# FPGA.net
KiCad netlist of a schematic drawn in EAGLE
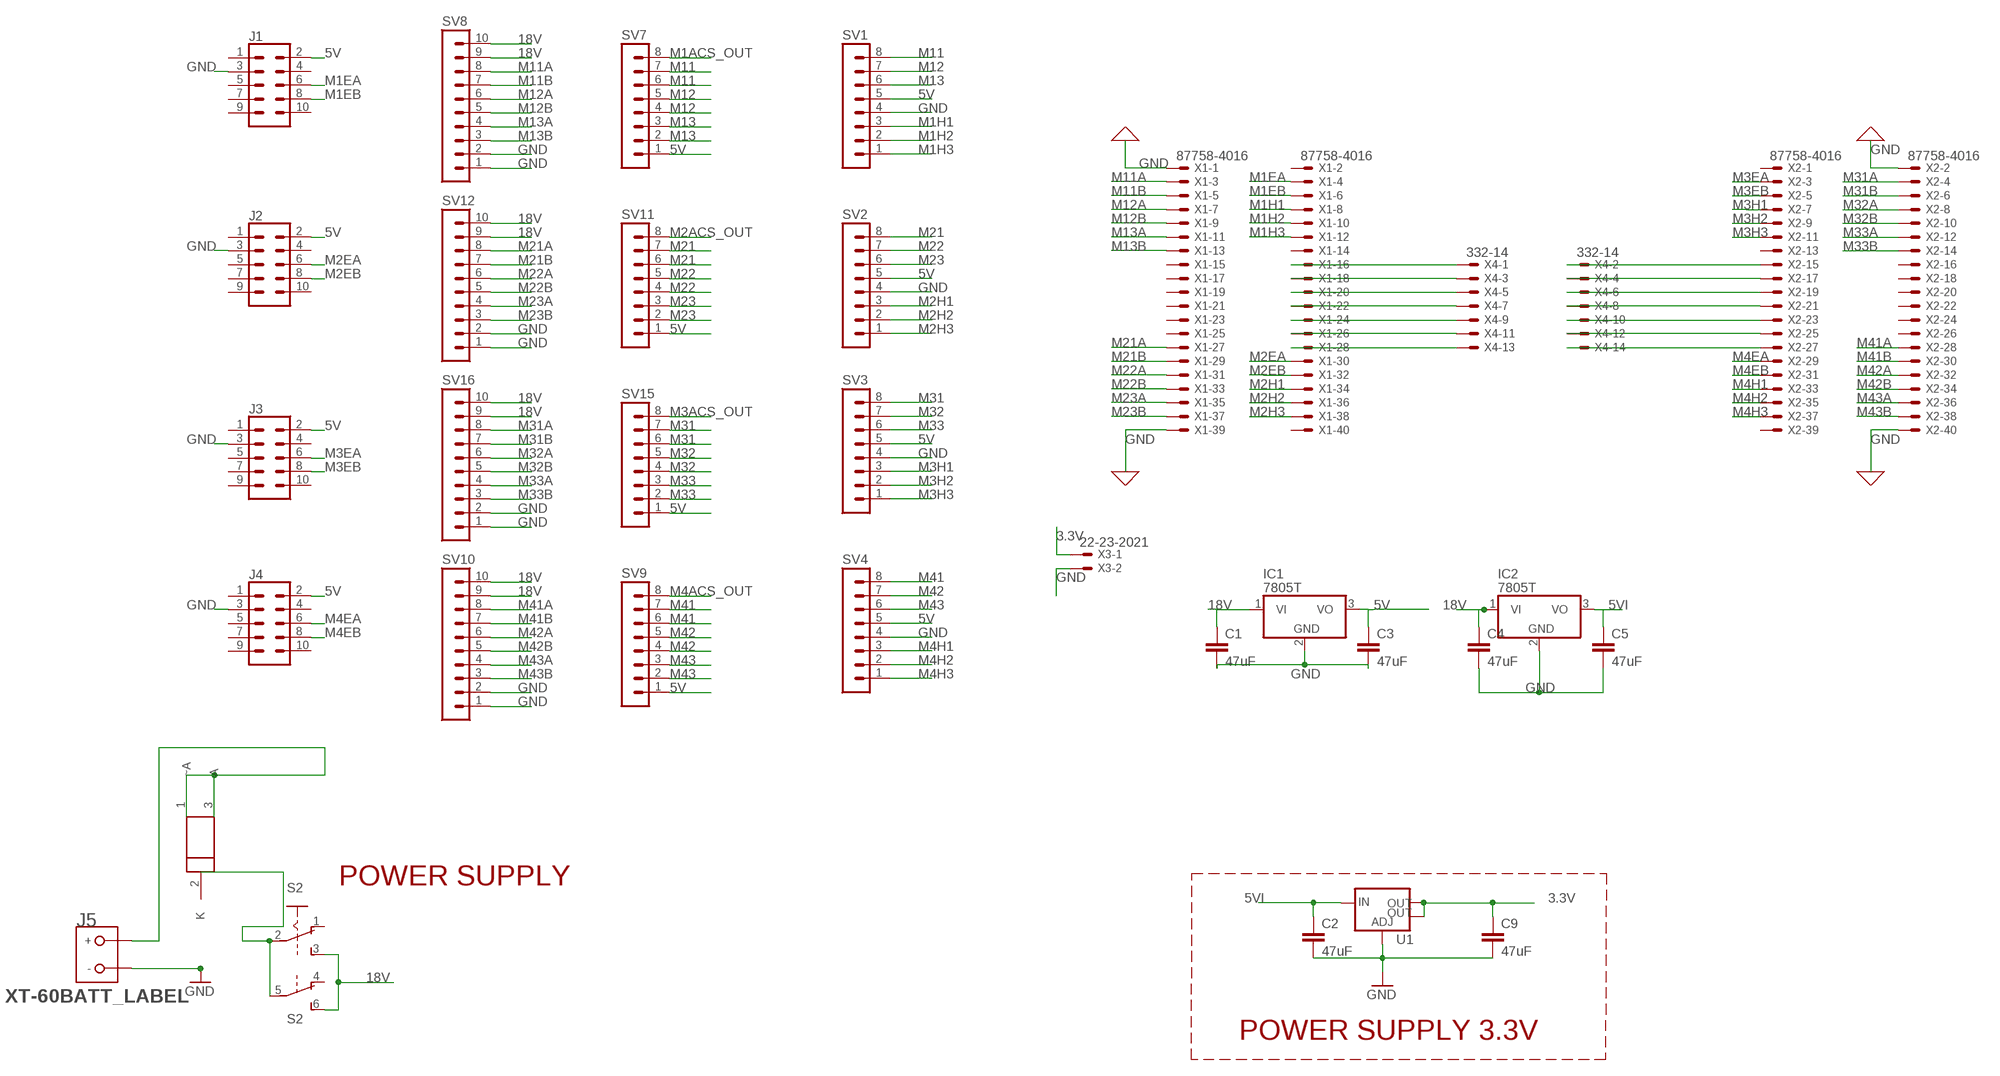
[diagram p0: schematic, sheet 1]

(export (version "E")
  (design (tool "Eeschema 10.0.6"))
  (components
    (comp (ref "C1")
      (value "47uF")
      (footprint "eagle-import:C1206")
      (libsource (lib "eagle-import") (part "C-EUC1206"))
    )
    (comp (ref "C2")
      (value "47uF")
      (footprint "eagle-import:C1206")
      (libsource (lib "eagle-import") (part "C-EUC1206"))
    )
    (comp (ref "C3")
      (value "47uF")
      (footprint "eagle-import:C1206")
      (libsource (lib "eagle-import") (part "C-EUC1206"))
    )
    (comp (ref "C4")
      (value "47uF")
      (footprint "eagle-import:C1206")
      (libsource (lib "eagle-import") (part "C-EUC1206"))
    )
    (comp (ref "C5")
      (value "47uF")
      (footprint "eagle-import:C1206")
      (libsource (lib "eagle-import") (part "C-EUC1206"))
    )
    (comp (ref "C9")
      (value "47uF")
      (footprint "eagle-import:C1206")
      (libsource (lib "eagle-import") (part "C-EUC1206"))
    )
    (comp (ref "IC1")
      (value "7805T")
      (footprint "eagle-import:TO220H")
      (libsource (lib "eagle-import") (part "78T05"))
    )
    (comp (ref "IC2")
      (value "7805T")
      (footprint "eagle-import:TO220H")
      (libsource (lib "eagle-import") (part "78T05"))
    )
    (comp (ref "J1")
      (value "CONN_05X2SHD_LOCK")
      (footprint "eagle-import:2X5-SHROUDED_LOCK")
      (libsource (lib "eagle-import") (part "CONN_05X2SHD_LOCK"))
    )
    (comp (ref "J2")
      (value "CONN_05X2SHD_LOCK")
      (footprint "eagle-import:2X5-SHROUDED_LOCK")
      (libsource (lib "eagle-import") (part "CONN_05X2SHD_LOCK"))
    )
    (comp (ref "J3")
      (value "CONN_05X2SHD_LOCK")
      (footprint "eagle-import:2X5-SHROUDED_LOCK")
      (libsource (lib "eagle-import") (part "CONN_05X2SHD_LOCK"))
    )
    (comp (ref "J4")
      (value "CONN_05X2SHD_LOCK")
      (footprint "eagle-import:2X5-SHROUDED_LOCK")
      (libsource (lib "eagle-import") (part "CONN_05X2SHD_LOCK"))
    )
    (comp (ref "J5")
      (value "XT-60BATT_LABEL")
      (footprint "eagle-import:XT-60")
      (libsource (lib "eagle-import") (part "XT-60BATT_LABEL"))
    )
    (comp (ref "S2")
      (value "A68-A31")
      (footprint "eagle-import:A68-A31")
      (libsource (lib "eagle-import") (part "A68-A31"))
    )
    (comp (ref "SV1")
      (value "MA08-1")
      (footprint "eagle-import:MA08-1")
      (libsource (lib "eagle-import") (part "MA08-1"))
    )
    (comp (ref "SV2")
      (value "MA08-1")
      (footprint "eagle-import:MA08-1")
      (libsource (lib "eagle-import") (part "MA08-1"))
    )
    (comp (ref "SV3")
      (value "MA08-1")
      (footprint "eagle-import:MA08-1")
      (libsource (lib "eagle-import") (part "MA08-1"))
    )
    (comp (ref "SV4")
      (value "MA08-1")
      (footprint "eagle-import:MA08-1")
      (libsource (lib "eagle-import") (part "MA08-1"))
    )
    (comp (ref "SV7")
      (value "MA08-1")
      (footprint "eagle-import:MA08-1")
      (libsource (lib "eagle-import") (part "MA08-1"))
    )
    (comp (ref "SV8")
      (value "MA10-1")
      (footprint "eagle-import:MA10-1")
      (libsource (lib "eagle-import") (part "MA10-1"))
    )
    (comp (ref "SV9")
      (value "MA08-1")
      (footprint "eagle-import:MA08-1")
      (libsource (lib "eagle-import") (part "MA08-1"))
    )
    (comp (ref "SV10")
      (value "MA10-1")
      (footprint "eagle-import:MA10-1")
      (libsource (lib "eagle-import") (part "MA10-1"))
    )
    (comp (ref "SV11")
      (value "MA08-1")
      (footprint "eagle-import:MA08-1")
      (libsource (lib "eagle-import") (part "MA08-1"))
    )
    (comp (ref "SV12")
      (value "MA10-1")
      (footprint "eagle-import:MA10-1")
      (libsource (lib "eagle-import") (part "MA10-1"))
    )
    (comp (ref "SV15")
      (value "MA08-1")
      (footprint "eagle-import:MA08-1")
      (libsource (lib "eagle-import") (part "MA08-1"))
    )
    (comp (ref "SV16")
      (value "MA10-1")
      (footprint "eagle-import:MA10-1")
      (libsource (lib "eagle-import") (part "MA10-1"))
    )
    (comp (ref "U1")
      (value "V_REG_LM1117SOT223")
      (footprint "eagle-import:SOT223")
      (libsource (lib "eagle-import") (part "V_REG_LM1117SOT223"))
    )
    (comp (ref "U3")
      (value "LP38690DT-3.3")
      (footprint "eagle-import:TO228P1042X238-3N")
      (libsource (lib "eagle-import") (part "LP38690DT-3.3"))
    )
    (comp (ref "X1")
      (value "87758-4016")
      (footprint "eagle-import:87758-4016")
      (fields (field (name "MF") "MOLEX"))
      (libsource (lib "eagle-import") (part "87758-4016"))
    )
    (comp (ref "X2")
      (value "87758-4016")
      (footprint "eagle-import:87758-4016")
      (fields (field (name "MF") "MOLEX"))
      (libsource (lib "eagle-import") (part "87758-4016"))
    )
    (comp (ref "X3")
      (value "22-23-2021")
      (footprint "eagle-import:22-23-2021")
      (fields (field (name "MF") "MOLEX"))
      (libsource (lib "eagle-import") (part "22-23-2021"))
    )
    (comp (ref "X4")
      (value "332-14")
      (footprint "eagle-import:332-14")
      (libsource (lib "eagle-import") (part "332-14"))
    )
  )
  (nets
    (net (code "1") (name "/3.3V") (class "Default")
      (node (ref "C9") (pin "1") (pinfunction "1_1") (pintype "passive"))
      (node (ref "U1") (pin "2") (pinfunction "OUT_2") (pintype "output"))
      (node (ref "U1") (pin "4") (pinfunction "OUT_4") (pintype "output"))
      (node (ref "X3") (pin "1") (pinfunction "S_1") (pintype "passive"))
    )
    (net (code "2") (name "/5V") (class "Default")
      (node (ref "C3") (pin "1") (pinfunction "1_1") (pintype "passive"))
      (node (ref "IC1") (pin "3") (pinfunction "VO_3") (pintype "passive"))
      (node (ref "J1") (pin "2") (pinfunction "2_2") (pintype "passive"))
      (node (ref "J2") (pin "2") (pinfunction "2_2") (pintype "passive"))
      (node (ref "J3") (pin "2") (pinfunction "2_2") (pintype "passive"))
      (node (ref "J4") (pin "2") (pinfunction "2_2") (pintype "passive"))
      (node (ref "SV1") (pin "5") (pinfunction "5_5") (pintype "passive"))
      (node (ref "SV11") (pin "1") (pinfunction "1_1") (pintype "passive"))
      (node (ref "SV15") (pin "1") (pinfunction "1_1") (pintype "passive"))
      (node (ref "SV2") (pin "5") (pinfunction "5_5") (pintype "passive"))
      (node (ref "SV3") (pin "5") (pinfunction "5_5") (pintype "passive"))
      (node (ref "SV4") (pin "5") (pinfunction "5_5") (pintype "passive"))
      (node (ref "SV7") (pin "1") (pinfunction "1_1") (pintype "passive"))
      (node (ref "SV9") (pin "1") (pinfunction "1_1") (pintype "passive"))
    )
    (net (code "3") (name "/5VI") (class "Default")
      (node (ref "C2") (pin "1") (pinfunction "1_1") (pintype "passive"))
      (node (ref "C5") (pin "1") (pinfunction "1_1") (pintype "passive"))
      (node (ref "IC2") (pin "3") (pinfunction "VO_3") (pintype "passive"))
      (node (ref "U1") (pin "3") (pinfunction "IN_3") (pintype "input"))
    )
    (net (code "4") (name "/18V") (class "Default")
      (node (ref "C1") (pin "1") (pinfunction "1_1") (pintype "passive"))
      (node (ref "C4") (pin "1") (pinfunction "1_1") (pintype "passive"))
      (node (ref "IC1") (pin "1") (pinfunction "VI_1") (pintype "input"))
      (node (ref "IC2") (pin "1") (pinfunction "VI_1") (pintype "input"))
      (node (ref "S2") (pin "3") (pinfunction "S_3") (pintype "passive"))
      (node (ref "S2") (pin "6") (pinfunction "S_6") (pintype "passive"))
      (node (ref "SV10") (pin "10") (pinfunction "10_10") (pintype "passive"))
      (node (ref "SV10") (pin "9") (pinfunction "9_9") (pintype "passive"))
      (node (ref "SV12") (pin "10") (pinfunction "10_10") (pintype "passive"))
      (node (ref "SV12") (pin "9") (pinfunction "9_9") (pintype "passive"))
      (node (ref "SV16") (pin "10") (pinfunction "10_10") (pintype "passive"))
      (node (ref "SV16") (pin "9") (pinfunction "9_9") (pintype "passive"))
      (node (ref "SV8") (pin "10") (pinfunction "10_10") (pintype "passive"))
      (node (ref "SV8") (pin "9") (pinfunction "9_9") (pintype "passive"))
    )
    (net (code "5") (name "/M1ACS_OUT") (class "Default")
      (node (ref "SV7") (pin "8") (pinfunction "8_8") (pintype "passive"))
    )
    (net (code "6") (name "/M1EA") (class "Default")
      (node (ref "J1") (pin "6") (pinfunction "6_6") (pintype "passive"))
      (node (ref "X1") (pin "4") (pinfunction "S_4") (pintype "passive"))
    )
    (net (code "7") (name "/M1EB") (class "Default")
      (node (ref "J1") (pin "8") (pinfunction "8_8") (pintype "passive"))
      (node (ref "X1") (pin "6") (pinfunction "S_6") (pintype "passive"))
    )
    (net (code "8") (name "/M1H1") (class "Default")
      (node (ref "SV1") (pin "3") (pinfunction "3_3") (pintype "passive"))
      (node (ref "X1") (pin "8") (pinfunction "S_8") (pintype "passive"))
    )
    (net (code "9") (name "/M1H2") (class "Default")
      (node (ref "SV1") (pin "2") (pinfunction "2_2") (pintype "passive"))
      (node (ref "X1") (pin "10") (pinfunction "S_10") (pintype "passive"))
    )
    (net (code "10") (name "/M1H3") (class "Default")
      (node (ref "SV1") (pin "1") (pinfunction "1_1") (pintype "passive"))
      (node (ref "X1") (pin "12") (pinfunction "S_12") (pintype "passive"))
    )
    (net (code "11") (name "/M2ACS_OUT") (class "Default")
      (node (ref "SV11") (pin "8") (pinfunction "8_8") (pintype "passive"))
    )
    (net (code "12") (name "/M2EA") (class "Default")
      (node (ref "J2") (pin "6") (pinfunction "6_6") (pintype "passive"))
      (node (ref "X1") (pin "30") (pinfunction "S_30") (pintype "passive"))
    )
    (net (code "13") (name "/M2EB") (class "Default")
      (node (ref "J2") (pin "8") (pinfunction "8_8") (pintype "passive"))
      (node (ref "X1") (pin "32") (pinfunction "S_32") (pintype "passive"))
    )
    (net (code "14") (name "/M2H1") (class "Default")
      (node (ref "SV2") (pin "3") (pinfunction "3_3") (pintype "passive"))
      (node (ref "X1") (pin "34") (pinfunction "S_34") (pintype "passive"))
    )
    (net (code "15") (name "/M2H2") (class "Default")
      (node (ref "SV2") (pin "2") (pinfunction "2_2") (pintype "passive"))
      (node (ref "X1") (pin "36") (pinfunction "S_36") (pintype "passive"))
    )
    (net (code "16") (name "/M2H3") (class "Default")
      (node (ref "SV2") (pin "1") (pinfunction "1_1") (pintype "passive"))
      (node (ref "X1") (pin "38") (pinfunction "S_38") (pintype "passive"))
    )
    (net (code "17") (name "/M3ACS_OUT") (class "Default")
      (node (ref "SV15") (pin "8") (pinfunction "8_8") (pintype "passive"))
    )
    (net (code "18") (name "/M3EA") (class "Default")
      (node (ref "J3") (pin "6") (pinfunction "6_6") (pintype "passive"))
      (node (ref "X2") (pin "3") (pinfunction "S_3") (pintype "passive"))
    )
    (net (code "19") (name "/M3EB") (class "Default")
      (node (ref "J3") (pin "8") (pinfunction "8_8") (pintype "passive"))
      (node (ref "X2") (pin "5") (pinfunction "S_5") (pintype "passive"))
    )
    (net (code "20") (name "/M3H1") (class "Default")
      (node (ref "SV3") (pin "3") (pinfunction "3_3") (pintype "passive"))
      (node (ref "X2") (pin "7") (pinfunction "S_7") (pintype "passive"))
    )
    (net (code "21") (name "/M3H2") (class "Default")
      (node (ref "SV3") (pin "2") (pinfunction "2_2") (pintype "passive"))
      (node (ref "X2") (pin "9") (pinfunction "S_9") (pintype "passive"))
    )
    (net (code "22") (name "/M3H3") (class "Default")
      (node (ref "SV3") (pin "1") (pinfunction "1_1") (pintype "passive"))
      (node (ref "X2") (pin "11") (pinfunction "S_11") (pintype "passive"))
    )
    (net (code "23") (name "/M4ACS_OUT") (class "Default")
      (node (ref "SV9") (pin "8") (pinfunction "8_8") (pintype "passive"))
    )
    (net (code "24") (name "/M4EA") (class "Default")
      (node (ref "J4") (pin "6") (pinfunction "6_6") (pintype "passive"))
      (node (ref "X2") (pin "29") (pinfunction "S_29") (pintype "passive"))
    )
    (net (code "25") (name "/M4EB") (class "Default")
      (node (ref "J4") (pin "8") (pinfunction "8_8") (pintype "passive"))
      (node (ref "X2") (pin "31") (pinfunction "S_31") (pintype "passive"))
    )
    (net (code "26") (name "/M4H1") (class "Default")
      (node (ref "SV4") (pin "3") (pinfunction "3_3") (pintype "passive"))
      (node (ref "X2") (pin "33") (pinfunction "S_33") (pintype "passive"))
    )
    (net (code "27") (name "/M4H2") (class "Default")
      (node (ref "SV4") (pin "2") (pinfunction "2_2") (pintype "passive"))
      (node (ref "X2") (pin "35") (pinfunction "S_35") (pintype "passive"))
    )
    (net (code "28") (name "/M4H3") (class "Default")
      (node (ref "SV4") (pin "1") (pinfunction "1_1") (pintype "passive"))
      (node (ref "X2") (pin "37") (pinfunction "S_37") (pintype "passive"))
    )
    (net (code "29") (name "/M11") (class "Default")
      (node (ref "SV1") (pin "8") (pinfunction "8_8") (pintype "passive"))
      (node (ref "SV7") (pin "6") (pinfunction "6_6") (pintype "passive"))
      (node (ref "SV7") (pin "7") (pinfunction "7_7") (pintype "passive"))
    )
    (net (code "30") (name "/M11A") (class "Default")
      (node (ref "SV8") (pin "8") (pinfunction "8_8") (pintype "passive"))
      (node (ref "X1") (pin "3") (pinfunction "S_3") (pintype "passive"))
    )
    (net (code "31") (name "/M11B") (class "Default")
      (node (ref "SV8") (pin "7") (pinfunction "7_7") (pintype "passive"))
      (node (ref "X1") (pin "5") (pinfunction "S_5") (pintype "passive"))
    )
    (net (code "32") (name "/M12") (class "Default")
      (node (ref "SV1") (pin "7") (pinfunction "7_7") (pintype "passive"))
      (node (ref "SV7") (pin "4") (pinfunction "4_4") (pintype "passive"))
      (node (ref "SV7") (pin "5") (pinfunction "5_5") (pintype "passive"))
    )
    (net (code "33") (name "/M12A") (class "Default")
      (node (ref "SV8") (pin "6") (pinfunction "6_6") (pintype "passive"))
      (node (ref "X1") (pin "7") (pinfunction "S_7") (pintype "passive"))
    )
    (net (code "34") (name "/M12B") (class "Default")
      (node (ref "SV8") (pin "5") (pinfunction "5_5") (pintype "passive"))
      (node (ref "X1") (pin "9") (pinfunction "S_9") (pintype "passive"))
    )
    (net (code "35") (name "/M13") (class "Default")
      (node (ref "SV1") (pin "6") (pinfunction "6_6") (pintype "passive"))
      (node (ref "SV7") (pin "2") (pinfunction "2_2") (pintype "passive"))
      (node (ref "SV7") (pin "3") (pinfunction "3_3") (pintype "passive"))
    )
    (net (code "36") (name "/M13A") (class "Default")
      (node (ref "SV8") (pin "4") (pinfunction "4_4") (pintype "passive"))
      (node (ref "X1") (pin "11") (pinfunction "S_11") (pintype "passive"))
    )
    (net (code "37") (name "/M13B") (class "Default")
      (node (ref "SV8") (pin "3") (pinfunction "3_3") (pintype "passive"))
      (node (ref "X1") (pin "13") (pinfunction "S_13") (pintype "passive"))
    )
    (net (code "38") (name "/M21") (class "Default")
      (node (ref "SV11") (pin "6") (pinfunction "6_6") (pintype "passive"))
      (node (ref "SV11") (pin "7") (pinfunction "7_7") (pintype "passive"))
      (node (ref "SV2") (pin "8") (pinfunction "8_8") (pintype "passive"))
    )
    (net (code "39") (name "/M21A") (class "Default")
      (node (ref "SV12") (pin "8") (pinfunction "8_8") (pintype "passive"))
      (node (ref "X1") (pin "27") (pinfunction "S_27") (pintype "passive"))
    )
    (net (code "40") (name "/M21B") (class "Default")
      (node (ref "SV12") (pin "7") (pinfunction "7_7") (pintype "passive"))
      (node (ref "X1") (pin "29") (pinfunction "S_29") (pintype "passive"))
    )
    (net (code "41") (name "/M22") (class "Default")
      (node (ref "SV11") (pin "4") (pinfunction "4_4") (pintype "passive"))
      (node (ref "SV11") (pin "5") (pinfunction "5_5") (pintype "passive"))
      (node (ref "SV2") (pin "7") (pinfunction "7_7") (pintype "passive"))
    )
    (net (code "42") (name "/M22A") (class "Default")
      (node (ref "SV12") (pin "6") (pinfunction "6_6") (pintype "passive"))
      (node (ref "X1") (pin "31") (pinfunction "S_31") (pintype "passive"))
    )
    (net (code "43") (name "/M22B") (class "Default")
      (node (ref "SV12") (pin "5") (pinfunction "5_5") (pintype "passive"))
      (node (ref "X1") (pin "33") (pinfunction "S_33") (pintype "passive"))
    )
    (net (code "44") (name "/M23") (class "Default")
      (node (ref "SV11") (pin "2") (pinfunction "2_2") (pintype "passive"))
      (node (ref "SV11") (pin "3") (pinfunction "3_3") (pintype "passive"))
      (node (ref "SV2") (pin "6") (pinfunction "6_6") (pintype "passive"))
    )
    (net (code "45") (name "/M23A") (class "Default")
      (node (ref "SV12") (pin "4") (pinfunction "4_4") (pintype "passive"))
      (node (ref "X1") (pin "35") (pinfunction "S_35") (pintype "passive"))
    )
    (net (code "46") (name "/M23B") (class "Default")
      (node (ref "SV12") (pin "3") (pinfunction "3_3") (pintype "passive"))
      (node (ref "X1") (pin "37") (pinfunction "S_37") (pintype "passive"))
    )
    (net (code "47") (name "/M31") (class "Default")
      (node (ref "SV15") (pin "6") (pinfunction "6_6") (pintype "passive"))
      (node (ref "SV15") (pin "7") (pinfunction "7_7") (pintype "passive"))
      (node (ref "SV3") (pin "8") (pinfunction "8_8") (pintype "passive"))
    )
    (net (code "48") (name "/M31A") (class "Default")
      (node (ref "SV16") (pin "8") (pinfunction "8_8") (pintype "passive"))
      (node (ref "X2") (pin "4") (pinfunction "S_4") (pintype "passive"))
    )
    (net (code "49") (name "/M31B") (class "Default")
      (node (ref "SV16") (pin "7") (pinfunction "7_7") (pintype "passive"))
      (node (ref "X2") (pin "6") (pinfunction "S_6") (pintype "passive"))
    )
    (net (code "50") (name "/M32") (class "Default")
      (node (ref "SV15") (pin "4") (pinfunction "4_4") (pintype "passive"))
      (node (ref "SV15") (pin "5") (pinfunction "5_5") (pintype "passive"))
      (node (ref "SV3") (pin "7") (pinfunction "7_7") (pintype "passive"))
    )
    (net (code "51") (name "/M32A") (class "Default")
      (node (ref "SV16") (pin "6") (pinfunction "6_6") (pintype "passive"))
      (node (ref "X2") (pin "8") (pinfunction "S_8") (pintype "passive"))
    )
    (net (code "52") (name "/M32B") (class "Default")
      (node (ref "SV16") (pin "5") (pinfunction "5_5") (pintype "passive"))
      (node (ref "X2") (pin "10") (pinfunction "S_10") (pintype "passive"))
    )
    (net (code "53") (name "/M33") (class "Default")
      (node (ref "SV15") (pin "2") (pinfunction "2_2") (pintype "passive"))
      (node (ref "SV15") (pin "3") (pinfunction "3_3") (pintype "passive"))
      (node (ref "SV3") (pin "6") (pinfunction "6_6") (pintype "passive"))
    )
    (net (code "54") (name "/M33A") (class "Default")
      (node (ref "SV16") (pin "4") (pinfunction "4_4") (pintype "passive"))
      (node (ref "X2") (pin "12") (pinfunction "S_12") (pintype "passive"))
    )
    (net (code "55") (name "/M33B") (class "Default")
      (node (ref "SV16") (pin "3") (pinfunction "3_3") (pintype "passive"))
      (node (ref "X2") (pin "14") (pinfunction "S_14") (pintype "passive"))
    )
    (net (code "56") (name "/M41") (class "Default")
      (node (ref "SV4") (pin "8") (pinfunction "8_8") (pintype "passive"))
      (node (ref "SV9") (pin "6") (pinfunction "6_6") (pintype "passive"))
      (node (ref "SV9") (pin "7") (pinfunction "7_7") (pintype "passive"))
    )
    (net (code "57") (name "/M41A") (class "Default")
      (node (ref "SV10") (pin "8") (pinfunction "8_8") (pintype "passive"))
      (node (ref "X2") (pin "28") (pinfunction "S_28") (pintype "passive"))
    )
    (net (code "58") (name "/M41B") (class "Default")
      (node (ref "SV10") (pin "7") (pinfunction "7_7") (pintype "passive"))
      (node (ref "X2") (pin "30") (pinfunction "S_30") (pintype "passive"))
    )
    (net (code "59") (name "/M42") (class "Default")
      (node (ref "SV4") (pin "7") (pinfunction "7_7") (pintype "passive"))
      (node (ref "SV9") (pin "4") (pinfunction "4_4") (pintype "passive"))
      (node (ref "SV9") (pin "5") (pinfunction "5_5") (pintype "passive"))
    )
    (net (code "60") (name "/M42A") (class "Default")
      (node (ref "SV10") (pin "6") (pinfunction "6_6") (pintype "passive"))
      (node (ref "X2") (pin "32") (pinfunction "S_32") (pintype "passive"))
    )
    (net (code "61") (name "/M42B") (class "Default")
      (node (ref "SV10") (pin "5") (pinfunction "5_5") (pintype "passive"))
      (node (ref "X2") (pin "34") (pinfunction "S_34") (pintype "passive"))
    )
    (net (code "62") (name "/M43") (class "Default")
      (node (ref "SV4") (pin "6") (pinfunction "6_6") (pintype "passive"))
      (node (ref "SV9") (pin "2") (pinfunction "2_2") (pintype "passive"))
      (node (ref "SV9") (pin "3") (pinfunction "3_3") (pintype "passive"))
    )
    (net (code "63") (name "/M43A") (class "Default")
      (node (ref "SV10") (pin "4") (pinfunction "4_4") (pintype "passive"))
      (node (ref "X2") (pin "36") (pinfunction "S_36") (pintype "passive"))
    )
    (net (code "64") (name "/M43B") (class "Default")
      (node (ref "SV10") (pin "3") (pinfunction "3_3") (pintype "passive"))
      (node (ref "X2") (pin "38") (pinfunction "S_38") (pintype "passive"))
    )
    (net (code "65") (name "GND") (class "Default")
      (node (ref "C1") (pin "2") (pinfunction "2_2") (pintype "passive"))
      (node (ref "C2") (pin "2") (pinfunction "2_2") (pintype "passive"))
      (node (ref "C3") (pin "2") (pinfunction "2_2") (pintype "passive"))
      (node (ref "C4") (pin "2") (pinfunction "2_2") (pintype "passive"))
      (node (ref "C5") (pin "2") (pinfunction "2_2") (pintype "passive"))
      (node (ref "C9") (pin "2") (pinfunction "2_2") (pintype "passive"))
      (node (ref "IC1") (pin "2") (pinfunction "GND_2") (pintype "passive"))
      (node (ref "IC2") (pin "2") (pinfunction "GND_2") (pintype "passive"))
      (node (ref "J1") (pin "3") (pinfunction "3_3") (pintype "passive"))
      (node (ref "J2") (pin "3") (pinfunction "3_3") (pintype "passive"))
      (node (ref "J3") (pin "3") (pinfunction "3_3") (pintype "passive"))
      (node (ref "J4") (pin "3") (pinfunction "3_3") (pintype "passive"))
      (node (ref "J5") (pin "GND") (pinfunction "-_GND") (pintype "passive"))
      (node (ref "SV1") (pin "4") (pinfunction "4_4") (pintype "passive"))
      (node (ref "SV10") (pin "1") (pinfunction "1_1") (pintype "passive"))
      (node (ref "SV10") (pin "2") (pinfunction "2_2") (pintype "passive"))
      (node (ref "SV12") (pin "1") (pinfunction "1_1") (pintype "passive"))
      (node (ref "SV12") (pin "2") (pinfunction "2_2") (pintype "passive"))
      (node (ref "SV16") (pin "1") (pinfunction "1_1") (pintype "passive"))
      (node (ref "SV16") (pin "2") (pinfunction "2_2") (pintype "passive"))
      (node (ref "SV2") (pin "4") (pinfunction "4_4") (pintype "passive"))
      (node (ref "SV3") (pin "4") (pinfunction "4_4") (pintype "passive"))
      (node (ref "SV4") (pin "4") (pinfunction "4_4") (pintype "passive"))
      (node (ref "SV8") (pin "1") (pinfunction "1_1") (pintype "passive"))
      (node (ref "SV8") (pin "2") (pinfunction "2_2") (pintype "passive"))
      (node (ref "U1") (pin "1") (pinfunction "ADJ_1") (pintype "input"))
      (node (ref "X1") (pin "1") (pinfunction "S_1") (pintype "passive"))
      (node (ref "X1") (pin "39") (pinfunction "S_39") (pintype "passive"))
      (node (ref "X2") (pin "2") (pinfunction "S_2") (pintype "passive"))
      (node (ref "X2") (pin "40") (pinfunction "S_40") (pintype "passive"))
      (node (ref "X3") (pin "2") (pinfunction "S_2") (pintype "passive"))
    )
    (net (code "66") (name "Net-(J5-+)") (class "Default")
      (node (ref "J5") (pin "BATT") (pinfunction "+_BATT") (pintype "passive"))
      (node (ref "U3") (pin "1") (pinfunction "~{A}_1") (pintype "bidirectional"))
      (node (ref "U3") (pin "3") (pinfunction "A_3") (pintype "bidirectional"))
    )
    (net (code "67") (name "Net-(S2A-P)") (class "Default")
      (node (ref "S2") (pin "2") (pinfunction "P_2") (pintype "passive"))
      (node (ref "S2") (pin "5") (pinfunction "P_5") (pintype "passive"))
      (node (ref "U3") (pin "2") (pinfunction "K_2") (pintype "bidirectional"))
    )
    (net (code "68") (name "Net-(X1H-S)") (class "Default")
      (node (ref "X1") (pin "16") (pinfunction "S_16") (pintype "passive"))
      (node (ref "X4") (pin "1") (pinfunction "S_1") (pintype "passive"))
    )
    (net (code "69") (name "Net-(X1J-S)") (class "Default")
      (node (ref "X1") (pin "18") (pinfunction "S_18") (pintype "passive"))
      (node (ref "X4") (pin "3") (pinfunction "S_3") (pintype "passive"))
    )
    (net (code "70") (name "Net-(X1M-S)") (class "Default")
      (node (ref "X1") (pin "20") (pinfunction "S_20") (pintype "passive"))
      (node (ref "X4") (pin "5") (pinfunction "S_5") (pintype "passive"))
    )
    (net (code "71") (name "Net-(X1O-S)") (class "Default")
      (node (ref "X1") (pin "22") (pinfunction "S_22") (pintype "passive"))
      (node (ref "X4") (pin "7") (pinfunction "S_7") (pintype "passive"))
    )
    (net (code "72") (name "Net-(X1Q-S)") (class "Default")
      (node (ref "X1") (pin "24") (pinfunction "S_24") (pintype "passive"))
      (node (ref "X4") (pin "9") (pinfunction "S_9") (pintype "passive"))
    )
    (net (code "73") (name "Net-(X1S-S)") (class "Default")
      (node (ref "X1") (pin "26") (pinfunction "S_26") (pintype "passive"))
      (node (ref "X4") (pin "11") (pinfunction "S_11") (pintype "passive"))
    )
    (net (code "74") (name "Net-(X1U-S)") (class "Default")
      (node (ref "X1") (pin "28") (pinfunction "S_28") (pintype "passive"))
      (node (ref "X4") (pin "13") (pinfunction "S_13") (pintype "passive"))
    )
    (net (code "75") (name "Net-(X2G-S)") (class "Default")
      (node (ref "X2") (pin "15") (pinfunction "S_15") (pintype "passive"))
      (node (ref "X4") (pin "2") (pinfunction "S_2") (pintype "passive"))
    )
    (net (code "76") (name "Net-(X2I-S)") (class "Default")
      (node (ref "X2") (pin "17") (pinfunction "S_17") (pintype "passive"))
      (node (ref "X4") (pin "4") (pinfunction "S_4") (pintype "passive"))
    )
    (net (code "77") (name "Net-(X2K-S)") (class "Default")
      (node (ref "X2") (pin "19") (pinfunction "S_19") (pintype "passive"))
      (node (ref "X4") (pin "6") (pinfunction "S_6") (pintype "passive"))
    )
    (net (code "78") (name "Net-(X2N-S)") (class "Default")
      (node (ref "X2") (pin "21") (pinfunction "S_21") (pintype "passive"))
      (node (ref "X4") (pin "8") (pinfunction "S_8") (pintype "passive"))
    )
    (net (code "79") (name "Net-(X2P-S)") (class "Default")
      (node (ref "X2") (pin "23") (pinfunction "S_23") (pintype "passive"))
      (node (ref "X4") (pin "10") (pinfunction "S_10") (pintype "passive"))
    )
    (net (code "80") (name "Net-(X2R-S)") (class "Default")
      (node (ref "X2") (pin "25") (pinfunction "S_25") (pintype "passive"))
      (node (ref "X4") (pin "12") (pinfunction "S_12") (pintype "passive"))
    )
    (net (code "81") (name "Net-(X2T-S)") (class "Default")
      (node (ref "X2") (pin "27") (pinfunction "S_27") (pintype "passive"))
      (node (ref "X4") (pin "14") (pinfunction "S_14") (pintype "passive"))
    )
    (net (code "82") (name "unconnected-(J1-Pad1)") (class "Default")
      (node (ref "J1") (pin "1") (pinfunction "1_1") (pintype "passive"))
    )
    (net (code "83") (name "unconnected-(J1-Pad4)") (class "Default")
      (node (ref "J1") (pin "4") (pinfunction "4_4") (pintype "passive"))
    )
    (net (code "84") (name "unconnected-(J1-Pad5)") (class "Default")
      (node (ref "J1") (pin "5") (pinfunction "5_5") (pintype "passive"))
    )
    (net (code "85") (name "unconnected-(J1-Pad7)") (class "Default")
      (node (ref "J1") (pin "7") (pinfunction "7_7") (pintype "passive"))
    )
    (net (code "86") (name "unconnected-(J1-Pad9)") (class "Default")
      (node (ref "J1") (pin "9") (pinfunction "9_9") (pintype "passive"))
    )
    (net (code "87") (name "unconnected-(J1-Pad10)") (class "Default")
      (node (ref "J1") (pin "10") (pinfunction "10_10") (pintype "passive"))
    )
    (net (code "88") (name "unconnected-(J2-Pad1)") (class "Default")
      (node (ref "J2") (pin "1") (pinfunction "1_1") (pintype "passive"))
    )
    (net (code "89") (name "unconnected-(J2-Pad4)") (class "Default")
      (node (ref "J2") (pin "4") (pinfunction "4_4") (pintype "passive"))
    )
    (net (code "90") (name "unconnected-(J2-Pad5)") (class "Default")
      (node (ref "J2") (pin "5") (pinfunction "5_5") (pintype "passive"))
    )
    (net (code "91") (name "unconnected-(J2-Pad7)") (class "Default")
      (node (ref "J2") (pin "7") (pinfunction "7_7") (pintype "passive"))
    )
    (net (code "92") (name "unconnected-(J2-Pad9)") (class "Default")
      (node (ref "J2") (pin "9") (pinfunction "9_9") (pintype "passive"))
    )
    (net (code "93") (name "unconnected-(J2-Pad10)") (class "Default")
      (node (ref "J2") (pin "10") (pinfunction "10_10") (pintype "passive"))
    )
    (net (code "94") (name "unconnected-(J3-Pad1)") (class "Default")
      (node (ref "J3") (pin "1") (pinfunction "1_1") (pintype "passive"))
    )
    (net (code "95") (name "unconnected-(J3-Pad4)") (class "Default")
      (node (ref "J3") (pin "4") (pinfunction "4_4") (pintype "passive"))
    )
    (net (code "96") (name "unconnected-(J3-Pad5)") (class "Default")
      (node (ref "J3") (pin "5") (pinfunction "5_5") (pintype "passive"))
    )
    (net (code "97") (name "unconnected-(J3-Pad7)") (class "Default")
      (node (ref "J3") (pin "7") (pinfunction "7_7") (pintype "passive"))
    )
    (net (code "98") (name "unconnected-(J3-Pad9)") (class "Default")
      (node (ref "J3") (pin "9") (pinfunction "9_9") (pintype "passive"))
    )
    (net (code "99") (name "unconnected-(J3-Pad10)") (class "Default")
      (node (ref "J3") (pin "10") (pinfunction "10_10") (pintype "passive"))
    )
    (net (code "100") (name "unconnected-(J4-Pad1)") (class "Default")
      (node (ref "J4") (pin "1") (pinfunction "1_1") (pintype "passive"))
    )
    (net (code "101") (name "unconnected-(J4-Pad4)") (class "Default")
      (node (ref "J4") (pin "4") (pinfunction "4_4") (pintype "passive"))
    )
    (net (code "102") (name "unconnected-(J4-Pad5)") (class "Default")
      (node (ref "J4") (pin "5") (pinfunction "5_5") (pintype "passive"))
    )
    (net (code "103") (name "unconnected-(J4-Pad7)") (class "Default")
      (node (ref "J4") (pin "7") (pinfunction "7_7") (pintype "passive"))
    )
    (net (code "104") (name "unconnected-(J4-Pad9)") (class "Default")
      (node (ref "J4") (pin "9") (pinfunction "9_9") (pintype "passive"))
    )
    (net (code "105") (name "unconnected-(J4-Pad10)") (class "Default")
      (node (ref "J4") (pin "10") (pinfunction "10_10") (pintype "passive"))
    )
    (net (code "106") (name "unconnected-(S2A-O-Pad1)") (class "Default")
      (node (ref "S2") (pin "1") (pinfunction "O_1") (pintype "passive"))
    )
    (net (code "107") (name "unconnected-(S2B-O-Pad4)") (class "Default")
      (node (ref "S2") (pin "4") (pinfunction "O_4") (pintype "passive"))
    )
    (net (code "108") (name "unconnected-(X1AI-S-Pad40)") (class "Default")
      (node (ref "X1") (pin "40") (pinfunction "S_40") (pintype "passive"))
    )
    (net (code "109") (name "unconnected-(X1F-S-Pad14)") (class "Default")
      (node (ref "X1") (pin "14") (pinfunction "S_14") (pintype "passive"))
    )
    (net (code "110") (name "unconnected-(X1G-S-Pad15)") (class "Default")
      (node (ref "X1") (pin "15") (pinfunction "S_15") (pintype "passive"))
    )
    (net (code "111") (name "unconnected-(X1I-S-Pad17)") (class "Default")
      (node (ref "X1") (pin "17") (pinfunction "S_17") (pintype "passive"))
    )
    (net (code "112") (name "unconnected-(X1K-S-Pad19)") (class "Default")
      (node (ref "X1") (pin "19") (pinfunction "S_19") (pintype "passive"))
    )
    (net (code "113") (name "unconnected-(X1L-S-Pad2)") (class "Default")
      (node (ref "X1") (pin "2") (pinfunction "S_2") (pintype "passive"))
    )
    (net (code "114") (name "unconnected-(X1N-S-Pad21)") (class "Default")
      (node (ref "X1") (pin "21") (pinfunction "S_21") (pintype "passive"))
    )
    (net (code "115") (name "unconnected-(X1P-S-Pad23)") (class "Default")
      (node (ref "X1") (pin "23") (pinfunction "S_23") (pintype "passive"))
    )
    (net (code "116") (name "unconnected-(X1R-S-Pad25)") (class "Default")
      (node (ref "X1") (pin "25") (pinfunction "S_25") (pintype "passive"))
    )
    (net (code "117") (name "unconnected-(X2A-S-Pad1)") (class "Default")
      (node (ref "X2") (pin "1") (pinfunction "S_1") (pintype "passive"))
    )
    (net (code "118") (name "unconnected-(X2AG-S-Pad39)") (class "Default")
      (node (ref "X2") (pin "39") (pinfunction "S_39") (pintype "passive"))
    )
    (net (code "119") (name "unconnected-(X2E-S-Pad13)") (class "Default")
      (node (ref "X2") (pin "13") (pinfunction "S_13") (pintype "passive"))
    )
    (net (code "120") (name "unconnected-(X2H-S-Pad16)") (class "Default")
      (node (ref "X2") (pin "16") (pinfunction "S_16") (pintype "passive"))
    )
    (net (code "121") (name "unconnected-(X2J-S-Pad18)") (class "Default")
      (node (ref "X2") (pin "18") (pinfunction "S_18") (pintype "passive"))
    )
    (net (code "122") (name "unconnected-(X2M-S-Pad20)") (class "Default")
      (node (ref "X2") (pin "20") (pinfunction "S_20") (pintype "passive"))
    )
    (net (code "123") (name "unconnected-(X2O-S-Pad22)") (class "Default")
      (node (ref "X2") (pin "22") (pinfunction "S_22") (pintype "passive"))
    )
    (net (code "124") (name "unconnected-(X2Q-S-Pad24)") (class "Default")
      (node (ref "X2") (pin "24") (pinfunction "S_24") (pintype "passive"))
    )
    (net (code "125") (name "unconnected-(X2S-S-Pad26)") (class "Default")
      (node (ref "X2") (pin "26") (pinfunction "S_26") (pintype "passive"))
    )
  )
)
